# Led_Lighting.net
KiCad netlist of a schematic drawn in Altium Designer
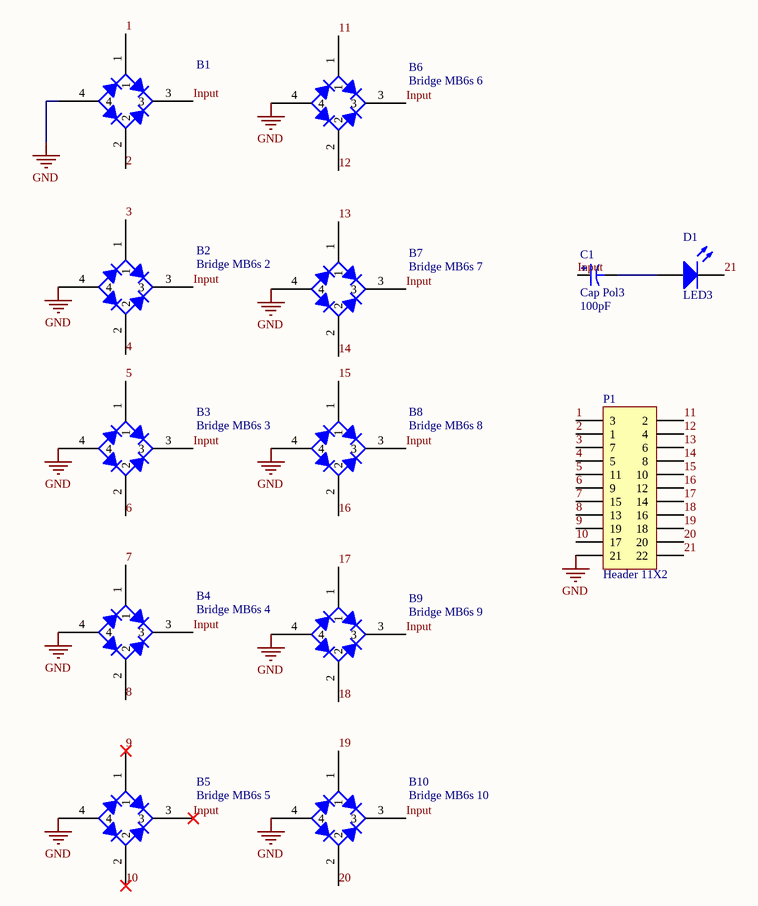
[diagram p0: Led Lighting.SchDoc]

(export (version "E")
  (design (tool "Eeschema 10.0.6"))
  (components
    (comp (ref "B1") (value "~") (footprint "MB6S") (libsource (lib "Led Lighting") (part "Bridge MB6s")))
    (comp (ref "B2")
      (value "Bridge MB6s 2")
      (footprint "MB6S")
      (libsource (lib "Led Lighting") (part "Bridge MB6s"))
    )
    (comp (ref "B3")
      (value "Bridge MB6s 3")
      (footprint "MB6S")
      (libsource (lib "Led Lighting") (part "Bridge MB6s"))
    )
    (comp (ref "B4")
      (value "Bridge MB6s 4")
      (footprint "MB6S")
      (libsource (lib "Led Lighting") (part "Bridge MB6s"))
    )
    (comp (ref "B5")
      (value "Bridge MB6s 5")
      (footprint "MB6S")
      (libsource (lib "Led Lighting") (part "Bridge MB6s"))
    )
    (comp (ref "B6")
      (value "Bridge MB6s 6")
      (footprint "MB6S")
      (libsource (lib "Led Lighting") (part "Bridge MB6s"))
    )
    (comp (ref "B7")
      (value "Bridge MB6s 7")
      (footprint "MB6S")
      (libsource (lib "Led Lighting") (part "Bridge MB6s"))
    )
    (comp (ref "B8")
      (value "Bridge MB6s 8")
      (footprint "MB6S")
      (libsource (lib "Led Lighting") (part "Bridge MB6s"))
    )
    (comp (ref "B9")
      (value "Bridge MB6s 9")
      (footprint "MB6S")
      (libsource (lib "Led Lighting") (part "Bridge MB6s"))
    )
    (comp (ref "B10")
      (value "Bridge MB6s 10")
      (footprint "MB6S")
      (libsource (lib "Led Lighting") (part "Bridge MB6s"))
    )
    (comp (ref "C1")
      (value "Cap Pol3")
      (footprint "C0805")
      (description "Polarized Capacitor (Surface Mount)")
      (fields (field (name "ALTIUM_VALUE") "100pF") (field (name "PUBLISHER") "Altium Limited"))
      (libsource (lib "Miscellaneous Devices") (part "Cap Pol3"))
    )
    (comp (ref "D1")
      (value "LED3")
      (footprint "3.5X2.8X1.9")
      (description "Typical BLUE SiC LED")
      (fields (field (name "PUBLISHER") "Altium Limited"))
      (libsource (lib "Miscellaneous Devices") (part "LED3"))
    )
    (comp (ref "P1")
      (value "Header 11X2")
      (footprint "HDR2X11")
      (description "Header, 11-Pin, Dual row")
      (fields (field (name "PUBLISHER") "Altium Limited"))
      (libsource (lib "Miscellaneous Connectors") (part "Header 11X2"))
    )
  )
  (nets
    (net (code "1") (name "/1") (class "Default")
      (node (ref "B1") (pin "1") (pinfunction "1_1") (pintype "passive"))
      (node (ref "P1") (pin "3") (pinfunction "3_3") (pintype "passive"))
    )
    (net (code "2") (name "/2") (class "Default")
      (node (ref "B1") (pin "2") (pinfunction "2_2") (pintype "passive"))
      (node (ref "P1") (pin "1") (pinfunction "1_1") (pintype "passive"))
    )
    (net (code "3") (name "/3") (class "Default")
      (node (ref "B2") (pin "1") (pinfunction "1_1") (pintype "passive"))
      (node (ref "P1") (pin "7") (pinfunction "7_7") (pintype "passive"))
    )
    (net (code "4") (name "/4") (class "Default")
      (node (ref "B2") (pin "2") (pinfunction "2_2") (pintype "passive"))
      (node (ref "P1") (pin "5") (pinfunction "5_5") (pintype "passive"))
    )
    (net (code "5") (name "/5") (class "Default")
      (node (ref "B3") (pin "1") (pinfunction "1_1") (pintype "passive"))
      (node (ref "P1") (pin "11") (pinfunction "11_11") (pintype "passive"))
    )
    (net (code "6") (name "/6") (class "Default")
      (node (ref "B3") (pin "2") (pinfunction "2_2") (pintype "passive"))
      (node (ref "P1") (pin "9") (pinfunction "9_9") (pintype "passive"))
    )
    (net (code "7") (name "/7") (class "Default")
      (node (ref "B4") (pin "1") (pinfunction "1_1") (pintype "passive"))
      (node (ref "P1") (pin "15") (pinfunction "15_15") (pintype "passive"))
    )
    (net (code "8") (name "/8") (class "Default")
      (node (ref "B4") (pin "2") (pinfunction "2_2") (pintype "passive"))
      (node (ref "P1") (pin "13") (pinfunction "13_13") (pintype "passive"))
    )
    (net (code "9") (name "/9") (class "Default")
      (node (ref "B5") (pin "1") (pinfunction "1_1") (pintype "passive"))
      (node (ref "P1") (pin "19") (pinfunction "19_19") (pintype "passive"))
    )
    (net (code "10") (name "/10") (class "Default")
      (node (ref "B5") (pin "2") (pinfunction "2_2") (pintype "passive"))
      (node (ref "P1") (pin "17") (pinfunction "17_17") (pintype "passive"))
    )
    (net (code "11") (name "/11") (class "Default")
      (node (ref "B6") (pin "1") (pinfunction "1_1") (pintype "passive"))
      (node (ref "P1") (pin "2") (pinfunction "2_2") (pintype "passive"))
    )
    (net (code "12") (name "/12") (class "Default")
      (node (ref "B6") (pin "2") (pinfunction "2_2") (pintype "passive"))
      (node (ref "P1") (pin "4") (pinfunction "4_4") (pintype "passive"))
    )
    (net (code "13") (name "/13") (class "Default")
      (node (ref "B7") (pin "1") (pinfunction "1_1") (pintype "passive"))
      (node (ref "P1") (pin "6") (pinfunction "6_6") (pintype "passive"))
    )
    (net (code "14") (name "/14") (class "Default")
      (node (ref "B7") (pin "2") (pinfunction "2_2") (pintype "passive"))
      (node (ref "P1") (pin "8") (pinfunction "8_8") (pintype "passive"))
    )
    (net (code "15") (name "/15") (class "Default")
      (node (ref "B8") (pin "1") (pinfunction "1_1") (pintype "passive"))
      (node (ref "P1") (pin "10") (pinfunction "10_10") (pintype "passive"))
    )
    (net (code "16") (name "/16") (class "Default")
      (node (ref "B8") (pin "2") (pinfunction "2_2") (pintype "passive"))
      (node (ref "P1") (pin "12") (pinfunction "12_12") (pintype "passive"))
    )
    (net (code "17") (name "/17") (class "Default")
      (node (ref "B9") (pin "1") (pinfunction "1_1") (pintype "passive"))
      (node (ref "P1") (pin "14") (pinfunction "14_14") (pintype "passive"))
    )
    (net (code "18") (name "/18") (class "Default")
      (node (ref "B9") (pin "2") (pinfunction "2_2") (pintype "passive"))
      (node (ref "P1") (pin "16") (pinfunction "16_16") (pintype "passive"))
    )
    (net (code "19") (name "/19") (class "Default")
      (node (ref "B10") (pin "1") (pinfunction "1_1") (pintype "passive"))
      (node (ref "P1") (pin "18") (pinfunction "18_18") (pintype "passive"))
    )
    (net (code "20") (name "/20") (class "Default")
      (node (ref "B10") (pin "2") (pinfunction "2_2") (pintype "passive"))
      (node (ref "P1") (pin "20") (pinfunction "20_20") (pintype "passive"))
    )
    (net (code "21") (name "/21") (class "Default")
      (node (ref "D1") (pin "2") (pinfunction "K_2") (pintype "passive"))
      (node (ref "P1") (pin "22") (pinfunction "22_22") (pintype "passive"))
    )
    (net (code "22") (name "/Input") (class "Default")
      (node (ref "B1") (pin "3") (pinfunction "3_3") (pintype "passive"))
      (node (ref "B10") (pin "3") (pinfunction "3_3") (pintype "passive"))
      (node (ref "B2") (pin "3") (pinfunction "3_3") (pintype "passive"))
      (node (ref "B3") (pin "3") (pinfunction "3_3") (pintype "passive"))
      (node (ref "B4") (pin "3") (pinfunction "3_3") (pintype "passive"))
      (node (ref "B5") (pin "3") (pinfunction "3_3") (pintype "passive"))
      (node (ref "B6") (pin "3") (pinfunction "3_3") (pintype "passive"))
      (node (ref "B7") (pin "3") (pinfunction "3_3") (pintype "passive"))
      (node (ref "B8") (pin "3") (pinfunction "3_3") (pintype "passive"))
      (node (ref "B9") (pin "3") (pinfunction "3_3") (pintype "passive"))
      (node (ref "C1") (pin "1") (pinfunction "1_1") (pintype "passive"))
    )
    (net (code "23") (name "GND") (class "Default")
      (node (ref "B1") (pin "4") (pinfunction "4_4") (pintype "passive"))
      (node (ref "B10") (pin "4") (pinfunction "4_4") (pintype "passive"))
      (node (ref "B2") (pin "4") (pinfunction "4_4") (pintype "passive"))
      (node (ref "B3") (pin "4") (pinfunction "4_4") (pintype "passive"))
      (node (ref "B4") (pin "4") (pinfunction "4_4") (pintype "passive"))
      (node (ref "B5") (pin "4") (pinfunction "4_4") (pintype "passive"))
      (node (ref "B6") (pin "4") (pinfunction "4_4") (pintype "passive"))
      (node (ref "B7") (pin "4") (pinfunction "4_4") (pintype "passive"))
      (node (ref "B8") (pin "4") (pinfunction "4_4") (pintype "passive"))
      (node (ref "B9") (pin "4") (pinfunction "4_4") (pintype "passive"))
      (node (ref "P1") (pin "21") (pinfunction "21_21") (pintype "passive"))
    )
    (net (code "24") (name "Net-(D1-A)") (class "Default")
      (node (ref "C1") (pin "2") (pinfunction "2_2") (pintype "passive"))
      (node (ref "D1") (pin "1") (pinfunction "A_1") (pintype "passive"))
    )
  )
)
